# OrangeSqueezer.net
KiCad netlist of a schematic drawn in EAGLE
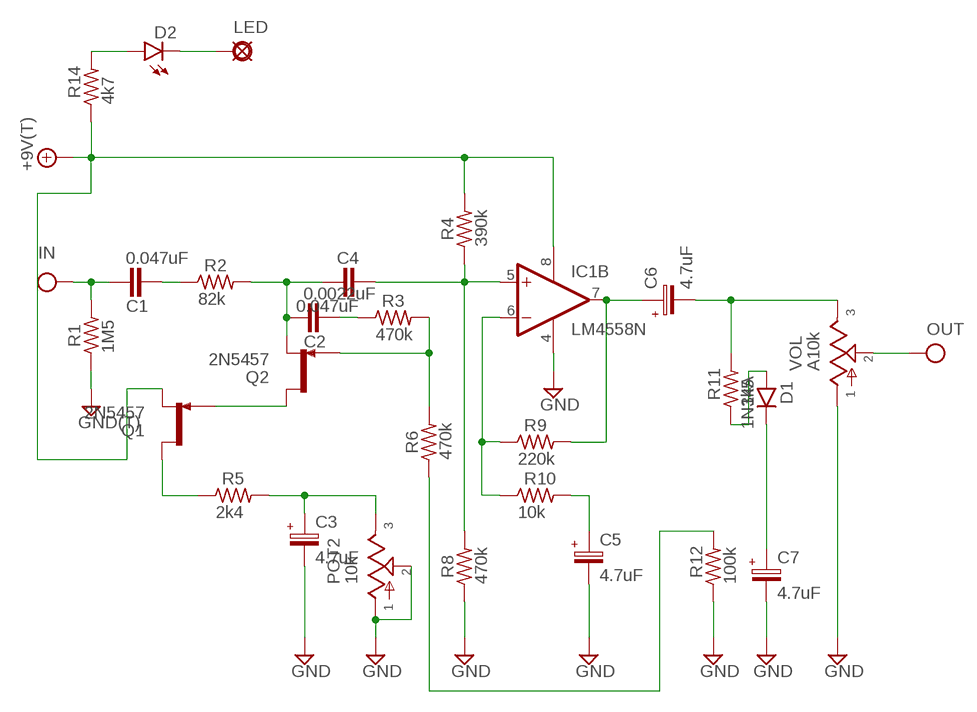
[diagram p0: schematic, sheet 1]

(export (version "E")
  (design (tool "Eeschema 10.0.6"))
  (components
    (comp (ref "+9V")
      (value "+9V(T)")
      (footprint "eagle-import:SQUARE")
      (libsource (lib "eagle-import") (part "+9V(T)"))
    )
    (comp (ref "C1")
      (value "0.047uF")
      (footprint "eagle-import:072X025")
      (libsource (lib "eagle-import") (part "072X0252"))
    )
    (comp (ref "C2")
      (value "0.0022uF")
      (footprint "eagle-import:072X025")
      (libsource (lib "eagle-import") (part "072X0252"))
    )
    (comp (ref "C3")
      (value "4.7uF")
      (footprint "eagle-import:050_020_1")
      (libsource (lib "eagle-import") (part "050-EU1"))
    )
    (comp (ref "C4")
      (value "0.047uF")
      (footprint "eagle-import:072X025")
      (libsource (lib "eagle-import") (part "072X0252"))
    )
    (comp (ref "C5")
      (value "4.7uF")
      (footprint "eagle-import:050_020_1")
      (libsource (lib "eagle-import") (part "050-EU1"))
    )
    (comp (ref "C6")
      (value "4.7uF")
      (footprint "eagle-import:050_020_1")
      (libsource (lib "eagle-import") (part "050-EU1"))
    )
    (comp (ref "C7")
      (value "4.7uF")
      (footprint "eagle-import:050_020_1")
      (libsource (lib "eagle-import") (part "050-EU1"))
    )
    (comp (ref "D1")
      (value "1N34A")
      (footprint "eagle-import:DO41-3")
      (libsource (lib "eagle-import") (part "1N400X.3"))
    )
    (comp (ref "D2")
      (value "LED3MM")
      (footprint "eagle-import:LED3MM")
      (libsource (lib "eagle-import") (part "LED3MM"))
    )
    (comp (ref "G")
      (value "GND(T)")
      (footprint "eagle-import:SQUARE")
      (libsource (lib "eagle-import") (part "GND(T)"))
    )
    (comp (ref "IC1")
      (value "LM4558N")
      (footprint "eagle-import:DIL08")
      (libsource (lib "eagle-import") (part "4558NLM"))
    )
    (comp (ref "IN")
      (value "IN(T)")
      (footprint "eagle-import:SQUARE")
      (libsource (lib "eagle-import") (part "IN(T)"))
    )
    (comp (ref "LED")
      (value "LED")
      (footprint "eagle-import:SQUARE")
      (libsource (lib "eagle-import") (part "PAD"))
    )
    (comp (ref "OUT")
      (value "OUT(T)")
      (footprint "eagle-import:SQUARE")
      (libsource (lib "eagle-import") (part "OUT(T)"))
    )
    (comp (ref "POT2")
      (value "10k")
      (footprint "eagle-import:B25P")
      (libsource (lib "eagle-import") (part "POTTRIM"))
    )
    (comp (ref "Q1")
      (value "2N5457")
      (footprint "eagle-import:TO92-")
      (libsource (lib "eagle-import") (part "2N5457"))
    )
    (comp (ref "Q2")
      (value "2N5457")
      (footprint "eagle-import:TO92-")
      (libsource (lib "eagle-import") (part "2N5457"))
    )
    (comp (ref "R1")
      (value "1M5")
      (footprint "eagle-import:R0207_3")
      (libsource (lib "eagle-import") (part "6MM.3"))
    )
    (comp (ref "R2")
      (value "82k")
      (footprint "eagle-import:R0207_3")
      (libsource (lib "eagle-import") (part "6MM.3"))
    )
    (comp (ref "R3")
      (value "470k")
      (footprint "eagle-import:R0207_3")
      (libsource (lib "eagle-import") (part "6MM.3"))
    )
    (comp (ref "R4")
      (value "390k")
      (footprint "eagle-import:R0207_3")
      (libsource (lib "eagle-import") (part "6MM.3"))
    )
    (comp (ref "R5")
      (value "2k4")
      (footprint "eagle-import:R0207_3")
      (libsource (lib "eagle-import") (part "6MM.3"))
    )
    (comp (ref "R6")
      (value "470k")
      (footprint "eagle-import:R0207_3")
      (libsource (lib "eagle-import") (part "6MM.3"))
    )
    (comp (ref "R8")
      (value "470k")
      (footprint "eagle-import:R0207_3")
      (libsource (lib "eagle-import") (part "6MM.3"))
    )
    (comp (ref "R9")
      (value "220k")
      (footprint "eagle-import:R0207_3")
      (libsource (lib "eagle-import") (part "6MM.3"))
    )
    (comp (ref "R10")
      (value "10k")
      (footprint "eagle-import:R0207_3")
      (libsource (lib "eagle-import") (part "6MM.3"))
    )
    (comp (ref "R11")
      (value "1k5")
      (footprint "eagle-import:R0207_3")
      (libsource (lib "eagle-import") (part "6MM.3"))
    )
    (comp (ref "R12")
      (value "100k")
      (footprint "eagle-import:R0207_3")
      (libsource (lib "eagle-import") (part "6MM.3"))
    )
    (comp (ref "R14")
      (value "4k7")
      (footprint "eagle-import:R0207_3")
      (libsource (lib "eagle-import") (part "6MM.3"))
    )
    (comp (ref "VOL")
      (value "A10k")
      (footprint "eagle-import:16MM_PCB_PADS")
      (libsource (lib "eagle-import") (part "POT16MM_PCB_PADS"))
    )
  )
  (nets
    (net (code "1") (name "+9V(T)") (class "Default")
      (node (ref "+9V") (pin "1") (pinfunction "+9V_1") (pintype "power_in"))
      (node (ref "IC1") (pin "8") (pinfunction "V+_8") (pintype "power_in"))
      (node (ref "Q1") (pin "2") (pinfunction "S_2") (pintype "passive"))
      (node (ref "R14") (pin "1") (pinfunction "1_1") (pintype "passive"))
      (node (ref "R4") (pin "2") (pinfunction "2_2") (pintype "passive"))
    )
    (net (code "2") (name "GND") (class "Default")
      (node (ref "C3") (pin "-") (pinfunction "-_-") (pintype "passive"))
      (node (ref "C5") (pin "-") (pinfunction "-_-") (pintype "passive"))
      (node (ref "C7") (pin "-") (pinfunction "-_-") (pintype "passive"))
      (node (ref "G") (pin "1") (pinfunction "GND_1") (pintype "power_in"))
      (node (ref "IC1") (pin "4") (pinfunction "V-_4") (pintype "power_in"))
      (node (ref "POT2") (pin "1") (pinfunction "1_1") (pintype "passive"))
      (node (ref "POT2") (pin "2") (pinfunction "2_2") (pintype "passive"))
      (node (ref "R1") (pin "1") (pinfunction "1_1") (pintype "passive"))
      (node (ref "R12") (pin "1") (pinfunction "1_1") (pintype "passive"))
      (node (ref "R8") (pin "1") (pinfunction "1_1") (pintype "passive"))
      (node (ref "VOL") (pin "1") (pinfunction "1_1") (pintype "passive"))
    )
    (net (code "3") (name "IN(T)") (class "Default")
      (node (ref "C1") (pin "2") (pinfunction "2_2") (pintype "passive"))
      (node (ref "IN") (pin "1") (pinfunction "IN_1") (pintype "power_in"))
      (node (ref "R1") (pin "2") (pinfunction "2_2") (pintype "passive"))
    )
    (net (code "4") (name "Net-(C1-Pad1)") (class "Default")
      (node (ref "C1") (pin "1") (pinfunction "1_1") (pintype "passive"))
      (node (ref "R2") (pin "1") (pinfunction "1_1") (pintype "passive"))
    )
    (net (code "5") (name "Net-(C2-Pad1)") (class "Default")
      (node (ref "C2") (pin "1") (pinfunction "1_1") (pintype "passive"))
      (node (ref "R3") (pin "1") (pinfunction "1_1") (pintype "passive"))
    )
    (net (code "6") (name "Net-(C3-Pad+)") (class "Default")
      (node (ref "C3") (pin "+") (pinfunction "+_+") (pintype "passive"))
      (node (ref "POT2") (pin "3") (pinfunction "3_3") (pintype "passive"))
      (node (ref "R5") (pin "2") (pinfunction "2_2") (pintype "passive"))
    )
    (net (code "7") (name "Net-(C5-Pad+)") (class "Default")
      (node (ref "C5") (pin "+") (pinfunction "+_+") (pintype "passive"))
      (node (ref "R10") (pin "2") (pinfunction "2_2") (pintype "passive"))
    )
    (net (code "8") (name "Net-(C6-Pad-)") (class "Default")
      (node (ref "C6") (pin "-") (pinfunction "-_-") (pintype "passive"))
      (node (ref "R11") (pin "2") (pinfunction "2_2") (pintype "passive"))
      (node (ref "VOL") (pin "3") (pinfunction "3_3") (pintype "passive"))
    )
    (net (code "9") (name "Net-(C7-Pad+)") (class "Default")
      (node (ref "C7") (pin "+") (pinfunction "+_+") (pintype "passive"))
      (node (ref "D1") (pin "C") (pinfunction "C_C") (pintype "passive"))
    )
    (net (code "10") (name "Net-(D1-PadA)") (class "Default")
      (node (ref "D1") (pin "A") (pinfunction "A_A") (pintype "passive"))
      (node (ref "R11") (pin "1") (pinfunction "1_1") (pintype "passive"))
    )
    (net (code "11") (name "Net-(D2-C)") (class "Default")
      (node (ref "D2") (pin "K") (pinfunction "C_K") (pintype "passive"))
      (node (ref "LED") (pin "1") (pinfunction "PAD_1") (pintype "passive"))
    )
    (net (code "12") (name "Net-(D2-PadA)") (class "Default")
      (node (ref "D2") (pin "A") (pinfunction "A_A") (pintype "passive"))
      (node (ref "R14") (pin "2") (pinfunction "2_2") (pintype "passive"))
    )
    (net (code "13") (name "Net-(IC1B-+IN)") (class "Default")
      (node (ref "C4") (pin "2") (pinfunction "2_2") (pintype "passive"))
      (node (ref "IC1") (pin "5") (pinfunction "+IN_5") (pintype "input"))
      (node (ref "R4") (pin "1") (pinfunction "1_1") (pintype "passive"))
      (node (ref "R8") (pin "2") (pinfunction "2_2") (pintype "passive"))
    )
    (net (code "14") (name "Net-(IC1B--IN)") (class "Default")
      (node (ref "IC1") (pin "6") (pinfunction "-IN_6") (pintype "input"))
      (node (ref "R10") (pin "1") (pinfunction "1_1") (pintype "passive"))
      (node (ref "R9") (pin "1") (pinfunction "1_1") (pintype "passive"))
    )
    (net (code "15") (name "Net-(IC1B-OUT)") (class "Default")
      (node (ref "C6") (pin "+") (pinfunction "+_+") (pintype "passive"))
      (node (ref "IC1") (pin "7") (pinfunction "OUT_7") (pintype "output"))
      (node (ref "R9") (pin "2") (pinfunction "2_2") (pintype "passive"))
    )
    (net (code "16") (name "Net-(Q1-D)") (class "Default")
      (node (ref "Q1") (pin "3") (pinfunction "D_3") (pintype "passive"))
      (node (ref "R5") (pin "1") (pinfunction "1_1") (pintype "passive"))
    )
    (net (code "17") (name "Net-(Q1-G)") (class "Default")
      (node (ref "Q1") (pin "1") (pinfunction "G_1") (pintype "passive"))
      (node (ref "Q2") (pin "3") (pinfunction "D_3") (pintype "passive"))
    )
    (net (code "18") (name "Net-(Q2-G)") (class "Default")
      (node (ref "Q2") (pin "1") (pinfunction "G_1") (pintype "passive"))
      (node (ref "R3") (pin "2") (pinfunction "2_2") (pintype "passive"))
      (node (ref "R6") (pin "2") (pinfunction "2_2") (pintype "passive"))
    )
    (net (code "19") (name "Net-(Q2-S)") (class "Default")
      (node (ref "C2") (pin "2") (pinfunction "2_2") (pintype "passive"))
      (node (ref "C4") (pin "1") (pinfunction "1_1") (pintype "passive"))
      (node (ref "Q2") (pin "2") (pinfunction "S_2") (pintype "passive"))
      (node (ref "R2") (pin "2") (pinfunction "2_2") (pintype "passive"))
    )
    (net (code "20") (name "Net-(R12-Pad2)") (class "Default")
      (node (ref "R12") (pin "2") (pinfunction "2_2") (pintype "passive"))
      (node (ref "R6") (pin "1") (pinfunction "1_1") (pintype "passive"))
    )
    (net (code "21") (name "OUT(T)") (class "Default")
      (node (ref "OUT") (pin "1") (pinfunction "OUT_1") (pintype "power_in"))
      (node (ref "VOL") (pin "2") (pinfunction "2_2") (pintype "passive"))
    )
  )
)
